# measure.net
KiCad netlist of a schematic drawn in EAGLE
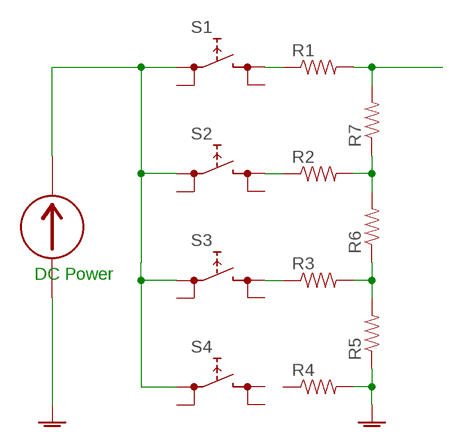
[diagram p0: schematic, sheet 1]

(export (version "E")
  (design (tool "Eeschema 10.0.6"))
  (components
    (comp (ref "DC_POEWR")
      (value "DCPOWER")
      (footprint "eagle-import:PS12")
      (libsource (lib "eagle-import") (part "DCPOWER"))
    )
    (comp (ref "R1")
      (value "RESISTORPTH-1/4W")
      (footprint "eagle-import:AXIAL-0.4")
      (libsource (lib "eagle-import") (part "RESISTORPTH-1/4W"))
    )
    (comp (ref "R2")
      (value "RESISTORPTH-1/4W")
      (footprint "eagle-import:AXIAL-0.4")
      (libsource (lib "eagle-import") (part "RESISTORPTH-1/4W"))
    )
    (comp (ref "R3")
      (value "RESISTORPTH-1/4W")
      (footprint "eagle-import:AXIAL-0.4")
      (libsource (lib "eagle-import") (part "RESISTORPTH-1/4W"))
    )
    (comp (ref "R4")
      (value "RESISTORPTH-1/4W")
      (footprint "eagle-import:AXIAL-0.4")
      (libsource (lib "eagle-import") (part "RESISTORPTH-1/4W"))
    )
    (comp (ref "R5")
      (value "RESISTORPTH-1/4W")
      (footprint "eagle-import:AXIAL-0.4")
      (libsource (lib "eagle-import") (part "RESISTORPTH-1/4W"))
    )
    (comp (ref "R6")
      (value "RESISTORPTH-1/4W")
      (footprint "eagle-import:AXIAL-0.4")
      (libsource (lib "eagle-import") (part "RESISTORPTH-1/4W"))
    )
    (comp (ref "R7")
      (value "RESISTORPTH-1/4W")
      (footprint "eagle-import:AXIAL-0.4")
      (libsource (lib "eagle-import") (part "RESISTORPTH-1/4W"))
    )
    (comp (ref "S1")
      (value "REKN")
      (footprint "eagle-import:REKN")
      (libsource (lib "eagle-import") (part "REKN"))
    )
    (comp (ref "S2")
      (value "REKN")
      (footprint "eagle-import:REKN")
      (libsource (lib "eagle-import") (part "REKN"))
    )
    (comp (ref "S3")
      (value "REKN")
      (footprint "eagle-import:REKN")
      (libsource (lib "eagle-import") (part "REKN"))
    )
    (comp (ref "S4")
      (value "REKN")
      (footprint "eagle-import:REKN")
      (libsource (lib "eagle-import") (part "REKN"))
    )
  )
  (nets
    (net (code "1") (name "AGND") (class "Default")
      (node (ref "DC_POEWR") (pin "P$1") (pinfunction "VGND_P$1") (pintype "output"))
      (node (ref "R4") (pin "P$2") (pinfunction "2_P$2") (pintype "passive"))
      (node (ref "R5") (pin "P$1") (pinfunction "1_P$1") (pintype "passive"))
    )
    (net (code "2") (name "Net-(DC_POEWR-VOUT)") (class "Default")
      (node (ref "DC_POEWR") (pin "P$2") (pinfunction "VOUT_P$2") (pintype "output"))
      (node (ref "S1") (pin "0A") (pinfunction "0_0A") (pintype "passive"))
      (node (ref "S2") (pin "0A") (pinfunction "0_0A") (pintype "passive"))
      (node (ref "S3") (pin "0A") (pinfunction "0_0A") (pintype "passive"))
      (node (ref "S4") (pin "0A") (pinfunction "0_0A") (pintype "passive"))
    )
    (net (code "3") (name "Net-(R1-1)") (class "Default")
      (node (ref "R1") (pin "P$1") (pinfunction "1_P$1") (pintype "passive"))
      (node (ref "S1") (pin "1A") (pinfunction "1_1A") (pintype "passive"))
    )
    (net (code "4") (name "Net-(R1-2)") (class "Default")
      (node (ref "R1") (pin "P$2") (pinfunction "2_P$2") (pintype "passive"))
      (node (ref "R7") (pin "P$2") (pinfunction "2_P$2") (pintype "passive"))
    )
    (net (code "5") (name "Net-(R2-1)") (class "Default")
      (node (ref "R2") (pin "P$1") (pinfunction "1_P$1") (pintype "passive"))
      (node (ref "S2") (pin "1A") (pinfunction "1_1A") (pintype "passive"))
    )
    (net (code "6") (name "Net-(R2-2)") (class "Default")
      (node (ref "R2") (pin "P$2") (pinfunction "2_P$2") (pintype "passive"))
      (node (ref "R6") (pin "P$2") (pinfunction "2_P$2") (pintype "passive"))
      (node (ref "R7") (pin "P$1") (pinfunction "1_P$1") (pintype "passive"))
    )
    (net (code "7") (name "Net-(R3-1)") (class "Default")
      (node (ref "R3") (pin "P$1") (pinfunction "1_P$1") (pintype "passive"))
      (node (ref "S3") (pin "1A") (pinfunction "1_1A") (pintype "passive"))
    )
    (net (code "8") (name "Net-(R3-2)") (class "Default")
      (node (ref "R3") (pin "P$2") (pinfunction "2_P$2") (pintype "passive"))
      (node (ref "R5") (pin "P$2") (pinfunction "2_P$2") (pintype "passive"))
      (node (ref "R6") (pin "P$1") (pinfunction "1_P$1") (pintype "passive"))
    )
    (net (code "9") (name "unconnected-(R4-1-PadP$1)") (class "Default")
      (node (ref "R4") (pin "P$1") (pinfunction "1_P$1") (pintype "passive"))
    )
    (net (code "10") (name "unconnected-(S1-0-Pad0B)") (class "Default")
      (node (ref "S1") (pin "0B") (pinfunction "0_0B") (pintype "passive"))
    )
    (net (code "11") (name "unconnected-(S1-1-Pad1B)") (class "Default")
      (node (ref "S1") (pin "1B") (pinfunction "1_1B") (pintype "passive"))
    )
    (net (code "12") (name "unconnected-(S2-0-Pad0B)") (class "Default")
      (node (ref "S2") (pin "0B") (pinfunction "0_0B") (pintype "passive"))
    )
    (net (code "13") (name "unconnected-(S2-1-Pad1B)") (class "Default")
      (node (ref "S2") (pin "1B") (pinfunction "1_1B") (pintype "passive"))
    )
    (net (code "14") (name "unconnected-(S3-0-Pad0B)") (class "Default")
      (node (ref "S3") (pin "0B") (pinfunction "0_0B") (pintype "passive"))
    )
    (net (code "15") (name "unconnected-(S3-1-Pad1B)") (class "Default")
      (node (ref "S3") (pin "1B") (pinfunction "1_1B") (pintype "passive"))
    )
    (net (code "16") (name "unconnected-(S4-0-Pad0B)") (class "Default")
      (node (ref "S4") (pin "0B") (pinfunction "0_0B") (pintype "passive"))
    )
    (net (code "17") (name "unconnected-(S4-1-Pad1A)") (class "Default")
      (node (ref "S4") (pin "1A") (pinfunction "1_1A") (pintype "passive"))
    )
    (net (code "18") (name "unconnected-(S4-1-Pad1B)") (class "Default")
      (node (ref "S4") (pin "1B") (pinfunction "1_1B") (pintype "passive"))
    )
  )
)
